# JTAG.net
KiCad netlist of a schematic drawn in Altium Designer
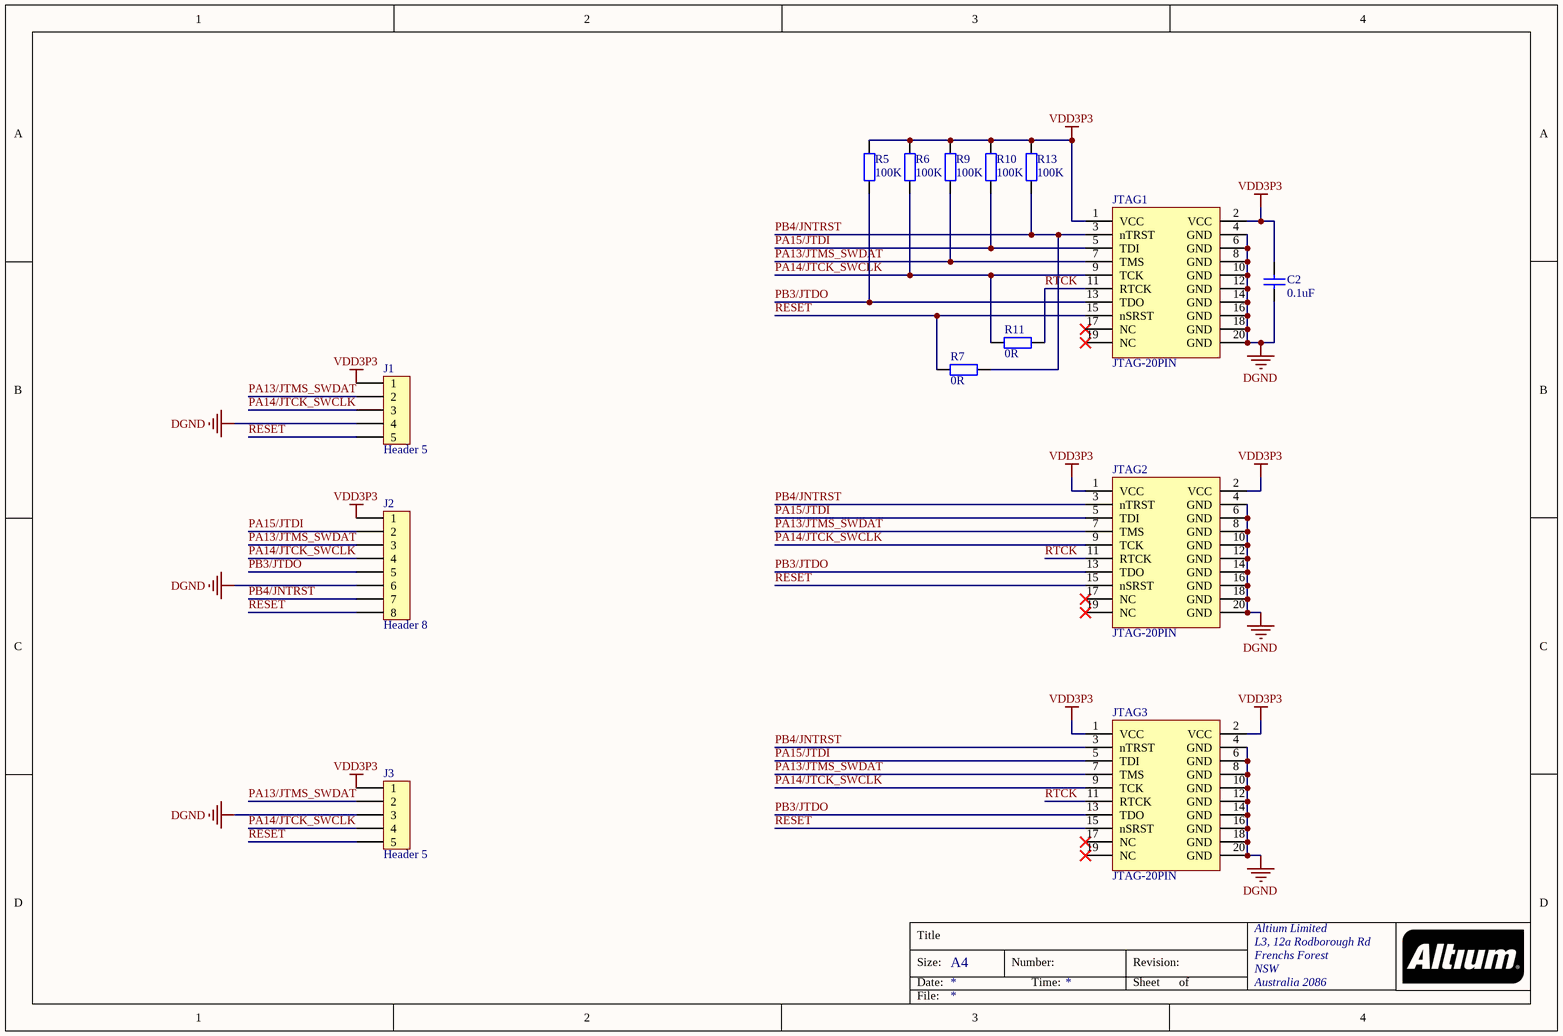
[diagram p0: JTAG.SchDoc]

(export (version "E")
  (design (tool "Eeschema 10.0.6"))
  (components
    (comp (ref "C2")
      (value "0.1uF")
      (footprint "CAPC1608X90N")
      (description "Capacitor")
      (fields (field (name "Comment") "Cap") (field (name "PUBLISHER") "Altium Limited"))
      (libsource (lib "CuiHQ_Library") (part "Cap"))
    )
    (comp (ref "J1")
      (value "Header 5")
      (footprint "HDR5X1_B1_1.25")
      (description "Header,5-Pin")
      (libsource (lib "CuiHQ_Library") (part "Header 5"))
    )
    (comp (ref "J2")
      (value "Header 8")
      (footprint "HDR8X1_B1_1.25")
      (description "Header, 8-Pin")
      (fields (field (name "PUBLISHER") "Altium Limited"))
      (libsource (lib "CuiHQ_Library") (part "Header 8"))
    )
    (comp (ref "J3")
      (value "Header 5")
      (footprint "HDR5X1_B1")
      (description "Header,5-Pin")
      (libsource (lib "CuiHQ_Library") (part "Header 5"))
    )
    (comp (ref "JTAG1")
      (value "JTAG-20PIN")
      (footprint "HDR10X2_E2")
      (description "ARM_JTAG-20PIN")
      (libsource (lib "CuiHQ_Library") (part "ARM_JTAG"))
    )
    (comp (ref "JTAG2")
      (value "JTAG-20PIN")
      (footprint "HDR10X2_A1")
      (description "ARM_JTAG-20PIN")
      (libsource (lib "CuiHQ_Library") (part "ARM_JTAG"))
    )
    (comp (ref "JTAG3")
      (value "JTAG-20PIN")
      (footprint "HDR10X2_A1")
      (description "ARM_JTAG-20PIN")
      (libsource (lib "CuiHQ_Library") (part "ARM_JTAG"))
    )
    (comp (ref "R5")
      (value "100K")
      (footprint "RESC1608X50N")
      (description "贴片电阻")
      (fields (field (name "Comment") "RES") (field (name "PUBLISHER") "Altium Limited"))
      (libsource (lib "CuiHQ_Library") (part "RES"))
    )
    (comp (ref "R6")
      (value "100K")
      (footprint "RESC1608X50N")
      (description "贴片电阻")
      (fields (field (name "Comment") "RES") (field (name "PUBLISHER") "Altium Limited"))
      (libsource (lib "CuiHQ_Library") (part "RES"))
    )
    (comp (ref "R7")
      (value "0R")
      (footprint "RESC1608X50N")
      (description "贴片电阻")
      (fields (field (name "Comment") "RES") (field (name "PUBLISHER") "Altium Limited"))
      (libsource (lib "") (part "RES_1"))
    )
    (comp (ref "R9")
      (value "100K")
      (footprint "RESC1608X50N")
      (description "贴片电阻")
      (fields (field (name "Comment") "RES") (field (name "PUBLISHER") "Altium Limited"))
      (libsource (lib "CuiHQ_Library") (part "RES"))
    )
    (comp (ref "R10")
      (value "100K")
      (footprint "RESC1608X50N")
      (description "贴片电阻")
      (fields (field (name "Comment") "RES") (field (name "PUBLISHER") "Altium Limited"))
      (libsource (lib "CuiHQ_Library") (part "RES"))
    )
    (comp (ref "R11")
      (value "0R")
      (footprint "RESC1608X50N")
      (description "贴片电阻")
      (fields (field (name "Comment") "RES") (field (name "PUBLISHER") "Altium Limited"))
      (libsource (lib "") (part "RES_1"))
    )
    (comp (ref "R13")
      (value "100K")
      (footprint "RESC1608X50N")
      (description "贴片电阻")
      (fields (field (name "Comment") "RES") (field (name "PUBLISHER") "Altium Limited"))
      (libsource (lib "CuiHQ_Library") (part "RES"))
    )
  )
  (nets
    (net (code "1") (name "/PA13{slash}JTMS_SWDAT") (class "Default")
      (node (ref "J1") (pin "2") (pinfunction "2_2") (pintype "passive"))
      (node (ref "J2") (pin "3") (pinfunction "3_3") (pintype "passive"))
      (node (ref "J3") (pin "2") (pinfunction "2_2") (pintype "passive"))
      (node (ref "JTAG1") (pin "7") (pinfunction "TMS_7") (pintype "passive"))
      (node (ref "JTAG2") (pin "7") (pinfunction "TMS_7") (pintype "passive"))
      (node (ref "JTAG3") (pin "7") (pinfunction "TMS_7") (pintype "passive"))
      (node (ref "R9") (pin "1") (pinfunction "1_1") (pintype "passive"))
    )
    (net (code "2") (name "/PA14{slash}JTCK_SWCLK") (class "Default")
      (node (ref "J1") (pin "3") (pinfunction "3_3") (pintype "passive"))
      (node (ref "J2") (pin "4") (pinfunction "4_4") (pintype "passive"))
      (node (ref "J3") (pin "4") (pinfunction "4_4") (pintype "passive"))
      (node (ref "JTAG1") (pin "9") (pinfunction "TCK_9") (pintype "passive"))
      (node (ref "JTAG2") (pin "9") (pinfunction "TCK_9") (pintype "passive"))
      (node (ref "JTAG3") (pin "9") (pinfunction "TCK_9") (pintype "passive"))
      (node (ref "R11") (pin "1") (pinfunction "1_1") (pintype "passive"))
      (node (ref "R6") (pin "1") (pinfunction "1_1") (pintype "passive"))
    )
    (net (code "3") (name "/PA15{slash}JTDI") (class "Default")
      (node (ref "J2") (pin "2") (pinfunction "2_2") (pintype "passive"))
      (node (ref "JTAG1") (pin "5") (pinfunction "TDI_5") (pintype "passive"))
      (node (ref "JTAG2") (pin "5") (pinfunction "TDI_5") (pintype "passive"))
      (node (ref "JTAG3") (pin "5") (pinfunction "TDI_5") (pintype "passive"))
      (node (ref "R10") (pin "1") (pinfunction "1_1") (pintype "passive"))
    )
    (net (code "4") (name "/PB3{slash}JTDO") (class "Default")
      (node (ref "J2") (pin "5") (pinfunction "5_5") (pintype "passive"))
      (node (ref "JTAG1") (pin "13") (pinfunction "TDO_13") (pintype "passive"))
      (node (ref "JTAG2") (pin "13") (pinfunction "TDO_13") (pintype "passive"))
      (node (ref "JTAG3") (pin "13") (pinfunction "TDO_13") (pintype "passive"))
      (node (ref "R5") (pin "1") (pinfunction "1_1") (pintype "passive"))
    )
    (net (code "5") (name "/PB4{slash}JNTRST") (class "Default")
      (node (ref "J2") (pin "7") (pinfunction "7_7") (pintype "passive"))
      (node (ref "JTAG1") (pin "3") (pinfunction "nTRST_3") (pintype "passive"))
      (node (ref "JTAG2") (pin "3") (pinfunction "nTRST_3") (pintype "passive"))
      (node (ref "JTAG3") (pin "3") (pinfunction "nTRST_3") (pintype "passive"))
      (node (ref "R13") (pin "1") (pinfunction "1_1") (pintype "passive"))
      (node (ref "R7") (pin "2") (pinfunction "2_2") (pintype "passive"))
    )
    (net (code "6") (name "/RESET") (class "Default")
      (node (ref "J1") (pin "5") (pinfunction "5_5") (pintype "passive"))
      (node (ref "J2") (pin "8") (pinfunction "8_8") (pintype "passive"))
      (node (ref "J3") (pin "5") (pinfunction "5_5") (pintype "passive"))
      (node (ref "JTAG1") (pin "15") (pinfunction "nSRST_15") (pintype "passive"))
      (node (ref "JTAG2") (pin "15") (pinfunction "nSRST_15") (pintype "passive"))
      (node (ref "JTAG3") (pin "15") (pinfunction "nSRST_15") (pintype "passive"))
      (node (ref "R7") (pin "1") (pinfunction "1_1") (pintype "passive"))
    )
    (net (code "7") (name "/RTCK") (class "Default")
      (node (ref "JTAG1") (pin "11") (pinfunction "RTCK_11") (pintype "passive"))
      (node (ref "JTAG2") (pin "11") (pinfunction "RTCK_11") (pintype "passive"))
      (node (ref "JTAG3") (pin "11") (pinfunction "RTCK_11") (pintype "passive"))
      (node (ref "R11") (pin "2") (pinfunction "2_2") (pintype "passive"))
    )
    (net (code "8") (name "DGND") (class "Default")
      (node (ref "C2") (pin "1") (pinfunction "1_1") (pintype "passive"))
      (node (ref "J1") (pin "4") (pinfunction "4_4") (pintype "passive"))
      (node (ref "J2") (pin "6") (pinfunction "6_6") (pintype "passive"))
      (node (ref "J3") (pin "3") (pinfunction "3_3") (pintype "passive"))
      (node (ref "JTAG1") (pin "10") (pinfunction "GND_10") (pintype "passive"))
      (node (ref "JTAG1") (pin "12") (pinfunction "GND_12") (pintype "passive"))
      (node (ref "JTAG1") (pin "14") (pinfunction "GND_14") (pintype "passive"))
      (node (ref "JTAG1") (pin "16") (pinfunction "GND_16") (pintype "passive"))
      (node (ref "JTAG1") (pin "18") (pinfunction "GND_18") (pintype "passive"))
      (node (ref "JTAG1") (pin "20") (pinfunction "GND_20") (pintype "passive"))
      (node (ref "JTAG1") (pin "4") (pinfunction "GND_4") (pintype "passive"))
      (node (ref "JTAG1") (pin "6") (pinfunction "GND_6") (pintype "passive"))
      (node (ref "JTAG1") (pin "8") (pinfunction "GND_8") (pintype "passive"))
      (node (ref "JTAG2") (pin "10") (pinfunction "GND_10") (pintype "passive"))
      (node (ref "JTAG2") (pin "12") (pinfunction "GND_12") (pintype "passive"))
      (node (ref "JTAG2") (pin "14") (pinfunction "GND_14") (pintype "passive"))
      (node (ref "JTAG2") (pin "16") (pinfunction "GND_16") (pintype "passive"))
      (node (ref "JTAG2") (pin "18") (pinfunction "GND_18") (pintype "passive"))
      (node (ref "JTAG2") (pin "20") (pinfunction "GND_20") (pintype "passive"))
      (node (ref "JTAG2") (pin "4") (pinfunction "GND_4") (pintype "passive"))
      (node (ref "JTAG2") (pin "6") (pinfunction "GND_6") (pintype "passive"))
      (node (ref "JTAG2") (pin "8") (pinfunction "GND_8") (pintype "passive"))
      (node (ref "JTAG3") (pin "10") (pinfunction "GND_10") (pintype "passive"))
      (node (ref "JTAG3") (pin "12") (pinfunction "GND_12") (pintype "passive"))
      (node (ref "JTAG3") (pin "14") (pinfunction "GND_14") (pintype "passive"))
      (node (ref "JTAG3") (pin "16") (pinfunction "GND_16") (pintype "passive"))
      (node (ref "JTAG3") (pin "18") (pinfunction "GND_18") (pintype "passive"))
      (node (ref "JTAG3") (pin "20") (pinfunction "GND_20") (pintype "passive"))
      (node (ref "JTAG3") (pin "4") (pinfunction "GND_4") (pintype "passive"))
      (node (ref "JTAG3") (pin "6") (pinfunction "GND_6") (pintype "passive"))
      (node (ref "JTAG3") (pin "8") (pinfunction "GND_8") (pintype "passive"))
    )
    (net (code "9") (name "VDD3P3") (class "Default")
      (node (ref "C2") (pin "2") (pinfunction "2_2") (pintype "passive"))
      (node (ref "J1") (pin "1") (pinfunction "1_1") (pintype "passive"))
      (node (ref "J2") (pin "1") (pinfunction "1_1") (pintype "passive"))
      (node (ref "J3") (pin "1") (pinfunction "1_1") (pintype "passive"))
      (node (ref "JTAG1") (pin "1") (pinfunction "VCC_1") (pintype "passive"))
      (node (ref "JTAG1") (pin "2") (pinfunction "VCC_2") (pintype "passive"))
      (node (ref "JTAG2") (pin "1") (pinfunction "VCC_1") (pintype "passive"))
      (node (ref "JTAG2") (pin "2") (pinfunction "VCC_2") (pintype "passive"))
      (node (ref "JTAG3") (pin "1") (pinfunction "VCC_1") (pintype "passive"))
      (node (ref "JTAG3") (pin "2") (pinfunction "VCC_2") (pintype "passive"))
      (node (ref "R10") (pin "2") (pinfunction "2_2") (pintype "passive"))
      (node (ref "R13") (pin "2") (pinfunction "2_2") (pintype "passive"))
      (node (ref "R5") (pin "2") (pinfunction "2_2") (pintype "passive"))
      (node (ref "R6") (pin "2") (pinfunction "2_2") (pintype "passive"))
      (node (ref "R9") (pin "2") (pinfunction "2_2") (pintype "passive"))
    )
    (net (code "10") (name "unconnected-(JTAG1-NC-Pad17)") (class "Default")
      (node (ref "JTAG1") (pin "17") (pinfunction "NC_17") (pintype "passive+no_connect"))
    )
    (net (code "11") (name "unconnected-(JTAG1-NC-Pad19)") (class "Default")
      (node (ref "JTAG1") (pin "19") (pinfunction "NC_19") (pintype "passive+no_connect"))
    )
    (net (code "12") (name "unconnected-(JTAG2-NC-Pad17)") (class "Default")
      (node (ref "JTAG2") (pin "17") (pinfunction "NC_17") (pintype "passive+no_connect"))
    )
    (net (code "13") (name "unconnected-(JTAG2-NC-Pad19)") (class "Default")
      (node (ref "JTAG2") (pin "19") (pinfunction "NC_19") (pintype "passive+no_connect"))
    )
    (net (code "14") (name "unconnected-(JTAG3-NC-Pad17)") (class "Default")
      (node (ref "JTAG3") (pin "17") (pinfunction "NC_17") (pintype "passive+no_connect"))
    )
    (net (code "15") (name "unconnected-(JTAG3-NC-Pad19)") (class "Default")
      (node (ref "JTAG3") (pin "19") (pinfunction "NC_19") (pintype "passive+no_connect"))
    )
  )
)
